# ESP_programmer.net
KiCad netlist of a schematic drawn in EAGLE
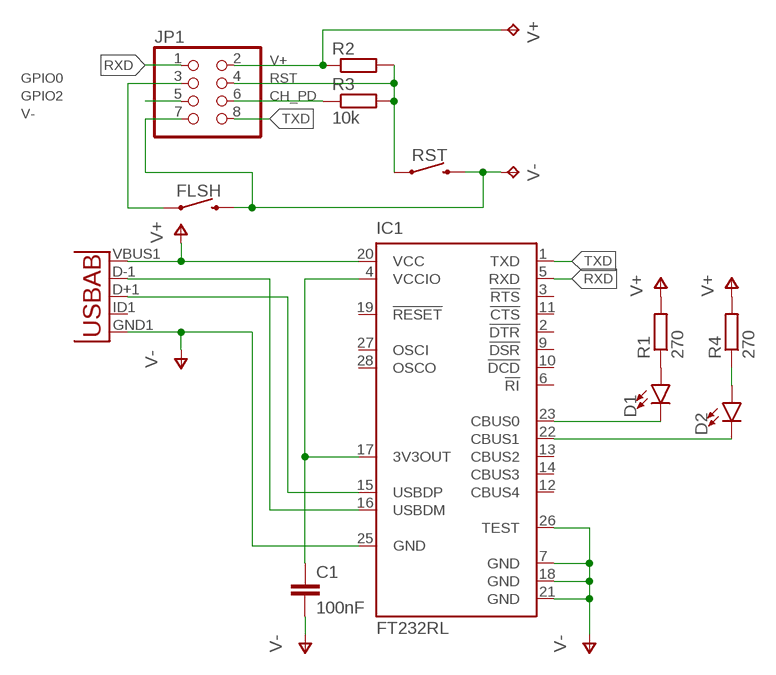
[diagram p0: schematic, sheet 1]

(export (version "E")
  (design (tool "Eeschema 10.0.6"))
  (components
    (comp (ref "C1")
      (value "100nF")
      (footprint "eagle-import:0603")
      (libsource (lib "eagle-import") (part "0.22UF-0603-25V-10%"))
    )
    (comp (ref "D1")
      (value "TX")
      (footprint "eagle-import:LED-0603")
      (libsource (lib "eagle-import") (part "LED-BLUE0603"))
    )
    (comp (ref "D2")
      (value "RX")
      (footprint "eagle-import:LED-0603")
      (libsource (lib "eagle-import") (part "LED-BLUE0603"))
    )
    (comp (ref "FLSH")
      (value "MOMENTARY-SWITCH-SPST-PTH-6.0MM")
      (footprint "eagle-import:TACTILE_SWITCH_PTH_6.0MM")
      (libsource (lib "eagle-import") (part "MOMENTARY-SWITCH-SPST-PTH-6.0MM"))
    )
    (comp (ref "IC1")
      (value "FT232RL")
      (footprint "eagle-import:SSOP28")
      (libsource (lib "eagle-import") (part "FT232RL"))
    )
    (comp (ref "JP1")
      (value "PINHD-2X4")
      (footprint "eagle-import:2X04")
      (libsource (lib "eagle-import") (part "PINHD-2X4"))
    )
    (comp (ref "R1")
      (value "270")
      (footprint "eagle-import:MINI_MELF-0102R")
      (libsource (lib "eagle-import") (part "R-EU_MELF0102R"))
    )
    (comp (ref "R2")
      (value "10k")
      (footprint "eagle-import:MINI_MELF-0102R")
      (libsource (lib "eagle-import") (part "R-EU_MELF0102R"))
    )
    (comp (ref "R3")
      (value "10k")
      (footprint "eagle-import:MINI_MELF-0102R")
      (libsource (lib "eagle-import") (part "R-EU_MELF0102R"))
    )
    (comp (ref "R4")
      (value "270")
      (footprint "eagle-import:MINI_MELF-0102R")
      (libsource (lib "eagle-import") (part "R-EU_MELF0102R"))
    )
    (comp (ref "RST")
      (value "MOMENTARY-SWITCH-SPST-PTH-6.0MM")
      (footprint "eagle-import:TACTILE_SWITCH_PTH_6.0MM")
      (libsource (lib "eagle-import") (part "MOMENTARY-SWITCH-SPST-PTH-6.0MM"))
    )
    (comp (ref "U1")
      (value "USB\"\"")
      (footprint "eagle-import:USB-MICRO-SMD")
      (libsource (lib "eagle-import") (part "USB{dblquote}{dblquote}"))
    )
    (comp (ref "V+")
      (value "TPB1,27")
      (footprint "eagle-import:B1,27")
      (libsource (lib "eagle-import") (part "TPB1,27"))
    )
    (comp (ref "V-")
      (value "TPB1,27")
      (footprint "eagle-import:B1,27")
      (libsource (lib "eagle-import") (part "TPB1,27"))
    )
  )
  (nets
    (net (code "1") (name "/CH_PD") (class "Default")
      (node (ref "JP1") (pin "6") (pinfunction "6_6") (pintype "passive"))
      (node (ref "R3") (pin "1") (pinfunction "1_1") (pintype "passive"))
    )
    (net (code "2") (name "/GPIO0") (class "Default")
      (node (ref "FLSH") (pin "1") (pinfunction "1_1") (pintype "passive"))
      (node (ref "JP1") (pin "3") (pinfunction "3_3") (pintype "passive"))
    )
    (net (code "3") (name "/GPIO2") (class "Default")
      (node (ref "JP1") (pin "5") (pinfunction "5_5") (pintype "passive"))
    )
    (net (code "4") (name "/RST") (class "Default")
      (node (ref "JP1") (pin "4") (pinfunction "4_4") (pintype "passive"))
      (node (ref "R2") (pin "2") (pinfunction "2_2") (pintype "passive"))
      (node (ref "R3") (pin "2") (pinfunction "2_2") (pintype "passive"))
      (node (ref "RST") (pin "1") (pinfunction "1_1") (pintype "passive"))
    )
    (net (code "5") (name "Net-(D1-PadA)") (class "Default")
      (node (ref "D1") (pin "A") (pinfunction "A_A") (pintype "passive"))
      (node (ref "R1") (pin "1") (pinfunction "1_1") (pintype "passive"))
    )
    (net (code "6") (name "Net-(D2-PadA)") (class "Default")
      (node (ref "D2") (pin "A") (pinfunction "A_A") (pintype "passive"))
      (node (ref "R4") (pin "1") (pinfunction "1_1") (pintype "passive"))
    )
    (net (code "7") (name "Net-(IC1-3V3OUT)") (class "Default")
      (node (ref "C1") (pin "1") (pinfunction "1_1") (pintype "passive"))
      (node (ref "IC1") (pin "17") (pinfunction "3V3OUT_17") (pintype "output"))
      (node (ref "IC1") (pin "4") (pinfunction "VCCIO_4") (pintype "power_in"))
    )
    (net (code "8") (name "Net-(IC1-CBUS0)") (class "Default")
      (node (ref "D1") (pin "C") (pinfunction "C_C") (pintype "passive"))
      (node (ref "IC1") (pin "23") (pinfunction "CBUS0_23") (pintype "bidirectional"))
    )
    (net (code "9") (name "Net-(IC1-CBUS1)") (class "Default")
      (node (ref "D2") (pin "C") (pinfunction "C_C") (pintype "passive"))
      (node (ref "IC1") (pin "22") (pinfunction "CBUS1_22") (pintype "bidirectional"))
    )
    (net (code "10") (name "Net-(IC1-USBDM)") (class "Default")
      (node (ref "IC1") (pin "16") (pinfunction "USBDM_16") (pintype "bidirectional"))
      (node (ref "U1") (pin "D-1") (pinfunction "D-_D-1") (pintype "bidirectional"))
    )
    (net (code "11") (name "Net-(IC1-USBDP)") (class "Default")
      (node (ref "IC1") (pin "15") (pinfunction "USBDP_15") (pintype "bidirectional"))
      (node (ref "U1") (pin "D+1") (pinfunction "D+_D+1") (pintype "bidirectional"))
    )
    (net (code "12") (name "RXD") (class "Default")
      (node (ref "IC1") (pin "5") (pinfunction "RXD_5") (pintype "input"))
      (node (ref "JP1") (pin "1") (pinfunction "1_1") (pintype "passive"))
    )
    (net (code "13") (name "TXD") (class "Default")
      (node (ref "IC1") (pin "1") (pinfunction "TXD_1") (pintype "output"))
      (node (ref "JP1") (pin "8") (pinfunction "8_8") (pintype "passive"))
    )
    (net (code "14") (name "V+") (class "Default")
      (node (ref "IC1") (pin "20") (pinfunction "VCC_20") (pintype "power_in"))
      (node (ref "JP1") (pin "2") (pinfunction "2_2") (pintype "passive"))
      (node (ref "R1") (pin "2") (pinfunction "2_2") (pintype "passive"))
      (node (ref "R2") (pin "1") (pinfunction "1_1") (pintype "passive"))
      (node (ref "R4") (pin "2") (pinfunction "2_2") (pintype "passive"))
      (node (ref "U1") (pin "VBUS1") (pinfunction "USB_VCC_VBUS1") (pintype "bidirectional"))
      (node (ref "V+") (pin "TP") (pinfunction "TP_TP") (pintype "input"))
    )
    (net (code "15") (name "V-") (class "Default")
      (node (ref "C1") (pin "2") (pinfunction "2_2") (pintype "passive"))
      (node (ref "FLSH") (pin "3") (pinfunction "2_3") (pintype "passive"))
      (node (ref "IC1") (pin "18") (pinfunction "GND_18") (pintype "power_in"))
      (node (ref "IC1") (pin "21") (pinfunction "GND_21") (pintype "power_in"))
      (node (ref "IC1") (pin "25") (pinfunction "GND_25") (pintype "power_in"))
      (node (ref "IC1") (pin "26") (pinfunction "TEST_26") (pintype "input"))
      (node (ref "IC1") (pin "7") (pinfunction "GND_7") (pintype "power_in"))
      (node (ref "JP1") (pin "7") (pinfunction "7_7") (pintype "passive"))
      (node (ref "RST") (pin "3") (pinfunction "2_3") (pintype "passive"))
      (node (ref "U1") (pin "GND1") (pinfunction "USB_GND_GND1") (pintype "bidirectional"))
      (node (ref "V-") (pin "TP") (pinfunction "TP_TP") (pintype "input"))
    )
    (net (code "16") (name "unconnected-(IC1-CBUS2-Pad13)") (class "Default")
      (node (ref "IC1") (pin "13") (pinfunction "CBUS2_13") (pintype "bidirectional"))
    )
    (net (code "17") (name "unconnected-(IC1-CBUS3-Pad14)") (class "Default")
      (node (ref "IC1") (pin "14") (pinfunction "CBUS3_14") (pintype "bidirectional"))
    )
    (net (code "18") (name "unconnected-(IC1-CBUS4-Pad12)") (class "Default")
      (node (ref "IC1") (pin "12") (pinfunction "CBUS4_12") (pintype "bidirectional"))
    )
    (net (code "19") (name "unconnected-(IC1-OSCI-Pad27)") (class "Default")
      (node (ref "IC1") (pin "27") (pinfunction "OSCI_27") (pintype "input"))
    )
    (net (code "20") (name "unconnected-(IC1-OSCO-Pad28)") (class "Default")
      (node (ref "IC1") (pin "28") (pinfunction "OSCO_28") (pintype "output"))
    )
    (net (code "21") (name "unconnected-(IC1-~{CTS}-Pad11)") (class "Default")
      (node (ref "IC1") (pin "11") (pinfunction "~{CTS}_11") (pintype "input"))
    )
    (net (code "22") (name "unconnected-(IC1-~{DCD}-Pad10)") (class "Default")
      (node (ref "IC1") (pin "10") (pinfunction "~{DCD}_10") (pintype "input"))
    )
    (net (code "23") (name "unconnected-(IC1-~{DSR}-Pad9)") (class "Default")
      (node (ref "IC1") (pin "9") (pinfunction "~{DSR}_9") (pintype "input"))
    )
    (net (code "24") (name "unconnected-(IC1-~{DTR}-Pad2)") (class "Default")
      (node (ref "IC1") (pin "2") (pinfunction "~{DTR}_2") (pintype "output"))
    )
    (net (code "25") (name "unconnected-(IC1-~{RESET}-Pad19)") (class "Default")
      (node (ref "IC1") (pin "19") (pinfunction "~{RESET}_19") (pintype "input"))
    )
    (net (code "26") (name "unconnected-(IC1-~{RI}-Pad6)") (class "Default")
      (node (ref "IC1") (pin "6") (pinfunction "~{RI}_6") (pintype "input"))
    )
    (net (code "27") (name "unconnected-(IC1-~{RTS}-Pad3)") (class "Default")
      (node (ref "IC1") (pin "3") (pinfunction "~{RTS}_3") (pintype "output"))
    )
    (net (code "28") (name "unconnected-(U1-NC-PadID1)") (class "Default")
      (node (ref "U1") (pin "ID1") (pinfunction "NC_ID1") (pintype "bidirectional"))
    )
  )
)
